# Sheet1.net
KiCad netlist of a schematic drawn in Altium Designer
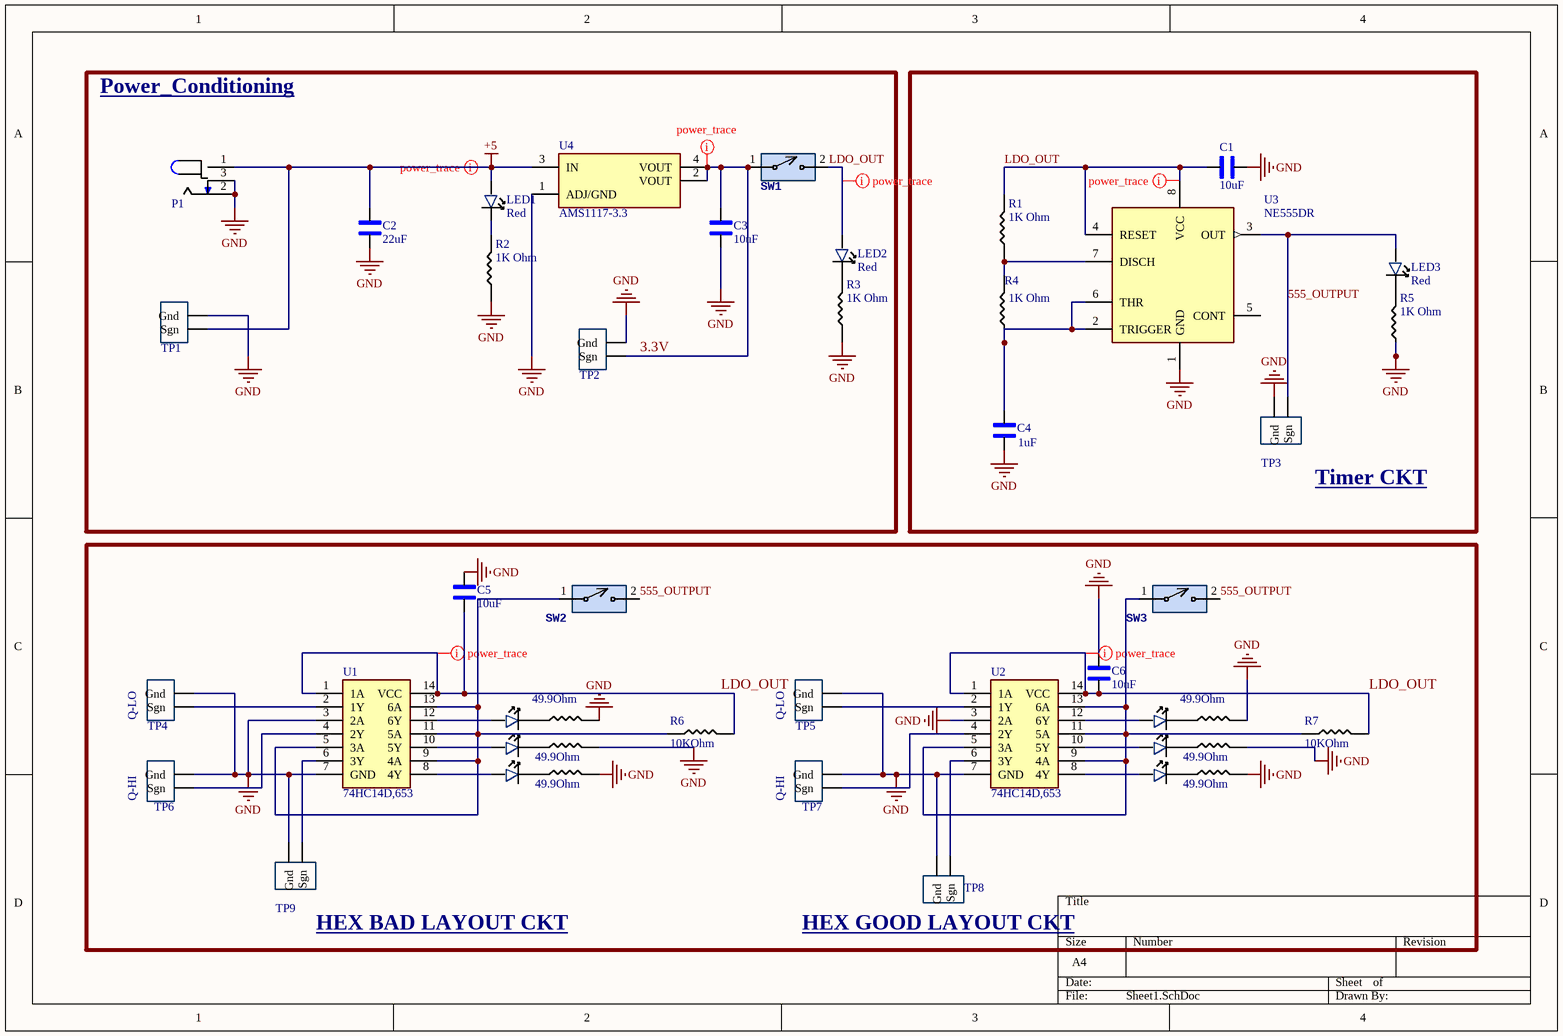
[diagram p0: Sheet1.SchDoc]

(export (version "E")
  (design (tool "Eeschema 10.0.6"))
  (components
    (comp (ref "C1")
      (value "10uF")
      (footprint "0402_Passive_Capacitor")
      (description "10uF ±20% 6.3V X5R 0402 Multilayer Ceramic Capacitors MLCC - SMD/SMT RoHS")
      (fields (field (name "MFR PART #") "CL05A106MQ5NUNC") (field (name "LCSC PART#") "C15525"))
      (libsource (lib "ECEN5730Lib_JLC_2021_07") (part "C_10uF_0402"))
    )
    (comp (ref "C2")
      (value "22uF")
      (footprint "0805_Passive_Capaciitor")
      (description "MULTILAYER CERAMIC CAPACITORS MLCC - SMD/SMT 22UF 25V 0805 ROHS")
      (fields (field (name "MFR PART #") "CL21A226MAQNNNE") (field (name "LCSC PART#") "C45783"))
      (libsource (lib "ECEN5730Lib_JLC_2021_07") (part "C_22uF_0805"))
    )
    (comp (ref "C3")
      (value "10uF")
      (footprint "0402_Passive_Capacitor")
      (description "10uF ±20% 6.3V X5R 0402 Multilayer Ceramic Capacitors MLCC - SMD/SMT RoHS")
      (fields (field (name "MFR PART #") "CL05A106MQ5NUNC") (field (name "LCSC PART#") "C15525"))
      (libsource (lib "ECEN5730Lib_JLC_2021_07") (part "C_10uF_0402"))
    )
    (comp (ref "C4")
      (value "1uF")
      (footprint "1206_Passive_Capacitor")
      (description "MULTILAYER CERAMIC CAPACITORS MLCC - SMD/SMT 1UF 50V 1206 ROHS")
      (fields (field (name "DIGIKEY PART") "399-8150-1-ND") (field (name "MFR PART #") "CL31B105KBHNNNE"))
      (libsource (lib "ECEN5730Lib_JLC_2021_07") (part "C_1uF_1206"))
    )
    (comp (ref "C5")
      (value "10uF")
      (footprint "0402_Passive_Capacitor")
      (description "10uF ±20% 6.3V X5R 0402 Multilayer Ceramic Capacitors MLCC - SMD/SMT RoHS")
      (fields (field (name "MFR PART #") "CL05A106MQ5NUNC") (field (name "LCSC PART#") "C15525"))
      (libsource (lib "ECEN5730Lib_JLC_2021_07") (part "C_10uF_0402"))
    )
    (comp (ref "C6")
      (value "10uF")
      (footprint "0402_Passive_Capacitor")
      (description "10uF ±20% 6.3V X5R 0402 Multilayer Ceramic Capacitors MLCC - SMD/SMT RoHS")
      (fields (field (name "MFR PART #") "CL05A106MQ5NUNC") (field (name "LCSC PART#") "C15525"))
      (libsource (lib "ECEN5730Lib_JLC_2021_07") (part "C_10uF_0402"))
    )
    (comp (ref "LED1")
      (value "Red")
      (footprint "LED_0603")
      (description "LIGHT EMITTING DIODES (LED) RED 520~625NM 90~100MCD@20MA TOP VIEW 0603 ROHS")
      (fields (field (name "MFR PART #") "KT-0603R") (field (name "LCSC PART#") "C2286"))
      (libsource (lib "ECEN5730Lib_JLC_2021_07") (part "LED_RED_0603"))
    )
    (comp (ref "LED2")
      (value "Red")
      (footprint "LED_0603")
      (description "LIGHT EMITTING DIODES (LED) RED 520~625NM 90~100MCD@20MA TOP VIEW 0603 ROHS")
      (fields (field (name "MFR PART #") "KT-0603R") (field (name "LCSC PART#") "C2286"))
      (libsource (lib "ECEN5730Lib_JLC_2021_07") (part "LED_RED_0603"))
    )
    (comp (ref "LED3")
      (value "Red")
      (footprint "LED_0603")
      (description "LIGHT EMITTING DIODES (LED) RED 520~625NM 90~100MCD@20MA TOP VIEW 0603 ROHS")
      (fields (field (name "MFR PART #") "KT-0603R") (field (name "LCSC PART#") "C2286"))
      (libsource (lib "ECEN5730Lib_JLC_2021_07") (part "LED_RED_0603"))
    )
    (comp (ref "LED4")
      (value "KT-0603R")
      (footprint "LED_0603")
      (description "LIGHT EMITTING DIODES (LED) RED 520~625NM 90~100MCD@20MA TOP VIEW 0603 ROHS")
      (fields (field (name "LCSC PART#") "C2286"))
      (libsource (lib "ECEN5730Lib_JLC_2021_07") (part "LED_RED_0603"))
    )
    (comp (ref "LED5")
      (value "KT-0603R")
      (footprint "LED_0603")
      (description "LIGHT EMITTING DIODES (LED) RED 520~625NM 90~100MCD@20MA TOP VIEW 0603 ROHS")
      (fields (field (name "LCSC PART#") "C2286"))
      (libsource (lib "ECEN5730Lib_JLC_2021_07") (part "LED_RED_0603"))
    )
    (comp (ref "LED6")
      (value "KT-0603R")
      (footprint "LED_0603")
      (description "LIGHT EMITTING DIODES (LED) RED 520~625NM 90~100MCD@20MA TOP VIEW 0603 ROHS")
      (fields (field (name "LCSC PART#") "C2286"))
      (libsource (lib "ECEN5730Lib_JLC_2021_07") (part "LED_RED_0603"))
    )
    (comp (ref "LED7")
      (value "KT-0603R")
      (footprint "LED_0603")
      (description "LIGHT EMITTING DIODES (LED) RED 520~625NM 90~100MCD@20MA TOP VIEW 0603 ROHS")
      (fields (field (name "LCSC PART#") "C2286"))
      (libsource (lib "ECEN5730Lib_JLC_2021_07") (part "LED_RED_0603"))
    )
    (comp (ref "LED8")
      (value "KT-0603R")
      (footprint "LED_0603")
      (description "LIGHT EMITTING DIODES (LED) RED 520~625NM 90~100MCD@20MA TOP VIEW 0603 ROHS")
      (fields (field (name "LCSC PART#") "C2286"))
      (libsource (lib "ECEN5730Lib_JLC_2021_07") (part "LED_RED_0603"))
    )
    (comp (ref "LED9")
      (value "KT-0603R")
      (footprint "LED_0603")
      (description "LIGHT EMITTING DIODES (LED) RED 520~625NM 90~100MCD@20MA TOP VIEW 0603 ROHS")
      (fields (field (name "LCSC PART#") "C2286"))
      (libsource (lib "ECEN5730Lib_JLC_2021_07") (part "LED_RED_0603"))
    )
    (comp (ref "P1")
      (value "Power Jack")
      (footprint "Power_Jack")
      (description "Power Barrel Connector Jack 2.10mm ID (0.083\"), 5.50mm OD (0.217\") Through Hole, Right Angle")
      (fields (field (name "DIGIKEY PART") "CP-102A-ND") (field (name "LCSC PART#") "C136744"))
      (libsource (lib "ECEN5730Lib_JLC_2021_07") (part "P_Power Jack"))
    )
    (comp (ref "R1")
      (value "1K Ohm")
      (footprint "1206_Passive_Resitor")
      (description "CHIP RESISTOR - SURFACE MOUNT 1KOHMS ±1% 1/4W 1206 ROHS")
      (fields (field (name "DIGIKEY PART") "RNCP1206FTD1K00CT-ND") (field (name "LCSC PART#") "C4410"))
      (libsource (lib "ECEN5730Lib_JLC_2021_07") (part "R_1K_1206"))
    )
    (comp (ref "R2")
      (value "1K Ohm")
      (footprint "1206_Passive_Resitor")
      (description "CHIP RESISTOR - SURFACE MOUNT 1KOHMS ±1% 1/4W 1206 ROHS")
      (fields (field (name "DIGIKEY PART") "RNCP1206FTD1K00CT-ND") (field (name "LCSC PART#") "C4410"))
      (libsource (lib "ECEN5730Lib_JLC_2021_07") (part "R_1K_1206"))
    )
    (comp (ref "R3")
      (value "1K Ohm")
      (footprint "1206_Passive_Resitor")
      (description "CHIP RESISTOR - SURFACE MOUNT 1KOHMS ±1% 1/4W 1206 ROHS")
      (fields (field (name "DIGIKEY PART") "RNCP1206FTD1K00CT-ND") (field (name "LCSC PART#") "C4410"))
      (libsource (lib "ECEN5730Lib_JLC_2021_07") (part "R_1K_1206"))
    )
    (comp (ref "R4")
      (value "1K Ohm")
      (footprint "1206_Passive_Resitor")
      (description "CHIP RESISTOR - SURFACE MOUNT 1KOHMS ±1% 1/4W 1206 ROHS")
      (fields (field (name "DIGIKEY PART") "RNCP1206FTD1K00CT-ND") (field (name "LCSC PART#") "C4410"))
      (libsource (lib "ECEN5730Lib_JLC_2021_07") (part "R_1K_1206"))
    )
    (comp (ref "R5")
      (value "1K Ohm")
      (footprint "1206_Passive_Resitor")
      (description "CHIP RESISTOR - SURFACE MOUNT 1KOHMS ±1% 1/4W 1206 ROHS")
      (fields (field (name "DIGIKEY PART") "RNCP1206FTD1K00CT-ND") (field (name "LCSC PART#") "C4410"))
      (libsource (lib "ECEN5730Lib_JLC_2021_07") (part "R_1K_1206"))
    )
    (comp (ref "R6")
      (value "10KOhm")
      (footprint "0402_Passive_Resistor")
      (description "CHIP RESISTOR - SURFACE MOUNT 10KOHMS ±1% 1/16W 0402 ROHS")
      (fields (field (name "MFR PART #") "0402WGF1002TCE") (field (name "LCSC PART#") "C25744"))
      (libsource (lib "ECEN5730Lib_JLC_2021_07") (part "R_10KOhm_0402"))
    )
    (comp (ref "R7")
      (value "10KOhm")
      (footprint "0402_Passive_Resistor")
      (description "CHIP RESISTOR - SURFACE MOUNT 10KOHMS ±1% 1/16W 0402 ROHS")
      (fields (field (name "MFR PART #") "0402WGF1002TCE") (field (name "LCSC PART#") "C25744"))
      (libsource (lib "ECEN5730Lib_JLC_2021_07") (part "R_10KOhm_0402"))
    )
    (comp (ref "R8")
      (value "49.9Ohm")
      (footprint "0402_Passive_Resistor")
      (description "CHIP RESISTOR - SURFACE MOUNT 49.9OHMS ±1% 1/16W 0402 ROHS")
      (fields (field (name "MFR PART #") "0402WGF499JTCE") (field (name "LCSC PART#") "C25120"))
      (libsource (lib "ECEN5730Lib_JLC_2021_07") (part "R_50Ohm_0402"))
    )
    (comp (ref "R9")
      (value "49.9Ohm")
      (footprint "0402_Passive_Resistor")
      (description "CHIP RESISTOR - SURFACE MOUNT 49.9OHMS ±1% 1/16W 0402 ROHS")
      (fields (field (name "MFR PART #") "0402WGF499JTCE") (field (name "LCSC PART#") "C25120"))
      (libsource (lib "ECEN5730Lib_JLC_2021_07") (part "R_50Ohm_0402"))
    )
    (comp (ref "R10")
      (value "49.9Ohm")
      (footprint "0402_Passive_Resistor")
      (description "CHIP RESISTOR - SURFACE MOUNT 49.9OHMS ±1% 1/16W 0402 ROHS")
      (fields (field (name "MFR PART #") "0402WGF499JTCE") (field (name "LCSC PART#") "C25120"))
      (libsource (lib "ECEN5730Lib_JLC_2021_07") (part "R_50Ohm_0402"))
    )
    (comp (ref "R11")
      (value "49.9Ohm")
      (footprint "0402_Passive_Resistor")
      (description "CHIP RESISTOR - SURFACE MOUNT 49.9OHMS ±1% 1/16W 0402 ROHS")
      (fields (field (name "MFR PART #") "0402WGF499JTCE") (field (name "LCSC PART#") "C25120"))
      (libsource (lib "ECEN5730Lib_JLC_2021_07") (part "R_50Ohm_0402"))
    )
    (comp (ref "R12")
      (value "49.9Ohm")
      (footprint "0402_Passive_Resistor")
      (description "CHIP RESISTOR - SURFACE MOUNT 49.9OHMS ±1% 1/16W 0402 ROHS")
      (fields (field (name "MFR PART #") "0402WGF499JTCE") (field (name "LCSC PART#") "C25120"))
      (libsource (lib "ECEN5730Lib_JLC_2021_07") (part "R_50Ohm_0402"))
    )
    (comp (ref "R13")
      (value "49.9Ohm")
      (footprint "0402_Passive_Resistor")
      (description "CHIP RESISTOR - SURFACE MOUNT 49.9OHMS ±1% 1/16W 0402 ROHS")
      (fields (field (name "MFR PART #") "0402WGF499JTCE") (field (name "LCSC PART#") "C25120"))
      (libsource (lib "ECEN5730Lib_JLC_2021_07") (part "R_50Ohm_0402"))
    )
    (comp (ref "SW1")
      (value "on_off_switch")
      (footprint "2Pin-Header-Conn")
      (description "2Pin Header")
      (fields (field (name "LCSC PART#") "C124375"))
      (libsource (lib "ECEN5730Lib_JLC_2021_07") (part "SW_2Pin_100mil_Switch"))
    )
    (comp (ref "SW2")
      (value "on_off_switch")
      (footprint "2Pin-Header-Conn")
      (description "2Pin Header")
      (fields (field (name "LCSC PART#") "C124375"))
      (libsource (lib "ECEN5730Lib_JLC_2021_07") (part "SW_2Pin_100mil_Switch"))
    )
    (comp (ref "SW3")
      (value "on_off_switch")
      (footprint "2Pin-Header-Conn")
      (description "2Pin Header")
      (fields (field (name "LCSC PART#") "C124375"))
      (libsource (lib "ECEN5730Lib_JLC_2021_07") (part "SW_2Pin_100mil_Switch"))
    )
    (comp (ref "TP1")
      (value "TP_5V")
      (footprint "TP10x_Probe")
      (description "Test Point 300 mil centers")
      (libsource (lib "ECEN5730Lib_Manual_2021_07") (part "TP_10x_Probe"))
    )
    (comp (ref "TP2")
      (value "TP_5V")
      (footprint "TP10x_Probe")
      (description "Test Point 300 mil centers")
      (libsource (lib "ECEN5730Lib_Manual_2021_07") (part "TP_10x_Probe"))
    )
    (comp (ref "TP3")
      (value "TP_555_OUTPUT")
      (footprint "TP10x_Probe")
      (description "Test Point 300 mil centers")
      (libsource (lib "") (part "TP_10x_Probe_1"))
    )
    (comp (ref "TP4")
      (value "TP_555_OUTPUT")
      (footprint "TP10x_Probe")
      (description "Test Point 300 mil centers")
      (libsource (lib "ECEN5730Lib_Manual_2021_07") (part "TP_10x_Probe"))
    )
    (comp (ref "TP5")
      (value "TP_555_OUTPUT")
      (footprint "TP10x_Probe")
      (description "Test Point 300 mil centers")
      (libsource (lib "ECEN5730Lib_Manual_2021_07") (part "TP_10x_Probe"))
    )
    (comp (ref "TP6")
      (value "TP_555_OUTPUT")
      (footprint "TP10x_Probe")
      (description "Test Point 300 mil centers")
      (libsource (lib "ECEN5730Lib_Manual_2021_07") (part "TP_10x_Probe"))
    )
    (comp (ref "TP7")
      (value "TP_555_OUTPUT")
      (footprint "TP10x_Probe")
      (description "Test Point 300 mil centers")
      (libsource (lib "ECEN5730Lib_Manual_2021_07") (part "TP_10x_Probe"))
    )
    (comp (ref "TP8")
      (value "TP_555_OUTPUT")
      (footprint "TP10x_Probe")
      (description "Test Point 300 mil centers")
      (libsource (lib "") (part "TP_10x_Probe_1"))
    )
    (comp (ref "TP9")
      (value "TP_555_OUTPUT")
      (footprint "TP10x_Probe")
      (description "Test Point 300 mil centers")
      (libsource (lib "") (part "TP_10x_Probe_1"))
    )
    (comp (ref "U1")
      (value "74HC14D,653")
      (footprint "HEX_74AC14")
      (description "Inverter IC 6 Channel Schmitt Trigger 14-SOIC")
      (fields (field (name "LCSC PART#") "C5605"))
      (libsource (lib "ECEN5730Lib_JLC_2021_08") (part "U_7414_HC_Hex"))
    )
    (comp (ref "U2")
      (value "74HC14D,653")
      (footprint "HEX_74AC14")
      (description "Inverter IC 6 Channel Schmitt Trigger 14-SOIC")
      (fields (field (name "LCSC PART#") "C5605"))
      (libsource (lib "ECEN5730Lib_JLC_2021_08") (part "U_7414_HC_Hex"))
    )
    (comp (ref "U3")
      (value "NE555DR")
      (footprint "TS555IDTTR")
      (description "555 Timer SOIC-8_150MIL ROHS 150ns Rise Time")
      (fields (field (name "LCSC PART#") "C7593"))
      (libsource (lib "ECEN5730Lib_JLC_2021_07") (part "U_555_Slow"))
    )
    (comp (ref "U4")
      (value "AMS1117-3.3")
      (footprint "LDO")
      (description "LOW DROPOUT REGULATORS(LDO) POSITIVE FIXED 1.3V @ 800MA 15V 3.3V 1A SOT-223 ROHS")
      (fields (field (name "LCSC PART#") "C6186"))
      (libsource (lib "ECEN5730Lib_JLC_2021_07") (part "PS_AMS_LDO_3v3"))
    )
  )
  (nets
    (net (code "1") (name "+5") (class "Default")
      (node (ref "C2") (pin "2") (pinfunction "2_2") (pintype "passive"))
      (node (ref "LED1") (pin "1") (pinfunction "1_1") (pintype "passive"))
      (node (ref "P1") (pin "1") (pinfunction "1_1") (pintype "power_in"))
      (node (ref "TP1") (pin "1") (pinfunction "Sgn_1") (pintype "passive"))
      (node (ref "U4") (pin "3") (pinfunction "IN_3") (pintype "power_in"))
    )
    (net (code "2") (name "/3.3V") (class "Default")
      (node (ref "C3") (pin "2") (pinfunction "2_2") (pintype "passive"))
      (node (ref "SW1") (pin "1") (pinfunction "1_1") (pintype "passive"))
      (node (ref "TP2") (pin "1") (pinfunction "Sgn_1") (pintype "passive"))
      (node (ref "U4") (pin "2") (pinfunction "VOUT_2") (pintype "power_in"))
      (node (ref "U4") (pin "4") (pinfunction "VOUT_4") (pintype "power_in"))
    )
    (net (code "3") (name "/555_OUTPUT") (class "Default")
      (node (ref "LED3") (pin "1") (pinfunction "1_1") (pintype "passive"))
      (node (ref "SW2") (pin "2") (pinfunction "2_2") (pintype "passive"))
      (node (ref "SW3") (pin "2") (pinfunction "2_2") (pintype "passive"))
      (node (ref "TP3") (pin "1") (pinfunction "Sgn_1") (pintype "passive"))
      (node (ref "U3") (pin "3") (pinfunction "OUT_3") (pintype "output"))
    )
    (net (code "4") (name "/LDO_OUT") (class "Default")
      (node (ref "C1") (pin "2") (pinfunction "2_2") (pintype "passive"))
      (node (ref "C5") (pin "2") (pinfunction "2_2") (pintype "passive"))
      (node (ref "C6") (pin "2") (pinfunction "2_2") (pintype "passive"))
      (node (ref "LED2") (pin "1") (pinfunction "1_1") (pintype "passive"))
      (node (ref "R1") (pin "2") (pinfunction "2_2") (pintype "passive"))
      (node (ref "R6") (pin "2") (pinfunction "2_2") (pintype "passive"))
      (node (ref "R7") (pin "2") (pinfunction "2_2") (pintype "passive"))
      (node (ref "SW1") (pin "2") (pinfunction "2_2") (pintype "passive"))
      (node (ref "U1") (pin "1") (pinfunction "1A_1") (pintype "passive"))
      (node (ref "U1") (pin "14") (pinfunction "VCC_14") (pintype "passive"))
      (node (ref "U2") (pin "1") (pinfunction "1A_1") (pintype "passive"))
      (node (ref "U2") (pin "14") (pinfunction "VCC_14") (pintype "passive"))
      (node (ref "U3") (pin "4") (pinfunction "RESET_4") (pintype "passive"))
      (node (ref "U3") (pin "8") (pinfunction "VCC_8") (pintype "power_in"))
    )
    (net (code "5") (name "GND") (class "Default")
      (node (ref "C1") (pin "1") (pinfunction "1_1") (pintype "passive"))
      (node (ref "C2") (pin "1") (pinfunction "1_1") (pintype "passive"))
      (node (ref "C3") (pin "1") (pinfunction "1_1") (pintype "passive"))
      (node (ref "C4") (pin "1") (pinfunction "1_1") (pintype "passive"))
      (node (ref "C5") (pin "1") (pinfunction "1_1") (pintype "passive"))
      (node (ref "C6") (pin "1") (pinfunction "1_1") (pintype "passive"))
      (node (ref "P1") (pin "2") (pinfunction "2_2") (pintype "power_in"))
      (node (ref "P1") (pin "3") (pinfunction "3_3") (pintype "power_in"))
      (node (ref "R10") (pin "2") (pinfunction "2_2") (pintype "passive"))
      (node (ref "R11") (pin "2") (pinfunction "2_2") (pintype "passive"))
      (node (ref "R12") (pin "2") (pinfunction "2_2") (pintype "passive"))
      (node (ref "R13") (pin "2") (pinfunction "2_2") (pintype "passive"))
      (node (ref "R2") (pin "1") (pinfunction "1_1") (pintype "passive"))
      (node (ref "R3") (pin "1") (pinfunction "1_1") (pintype "passive"))
      (node (ref "R5") (pin "1") (pinfunction "1_1") (pintype "passive"))
      (node (ref "R8") (pin "2") (pinfunction "2_2") (pintype "passive"))
      (node (ref "R9") (pin "2") (pinfunction "2_2") (pintype "passive"))
      (node (ref "TP1") (pin "2") (pinfunction "Gnd_2") (pintype "passive"))
      (node (ref "TP2") (pin "2") (pinfunction "Gnd_2") (pintype "passive"))
      (node (ref "TP3") (pin "2") (pinfunction "Gnd_2") (pintype "passive"))
      (node (ref "TP4") (pin "2") (pinfunction "Gnd_2") (pintype "passive"))
      (node (ref "TP5") (pin "2") (pinfunction "Gnd_2") (pintype "passive"))
      (node (ref "TP6") (pin "2") (pinfunction "Gnd_2") (pintype "passive"))
      (node (ref "TP7") (pin "2") (pinfunction "Gnd_2") (pintype "passive"))
      (node (ref "TP8") (pin "2") (pinfunction "Gnd_2") (pintype "passive"))
      (node (ref "TP9") (pin "2") (pinfunction "Gnd_2") (pintype "passive"))
      (node (ref "U1") (pin "3") (pinfunction "2A_3") (pintype "passive"))
      (node (ref "U1") (pin "7") (pinfunction "GND_7") (pintype "passive"))
      (node (ref "U2") (pin "3") (pinfunction "2A_3") (pintype "passive"))
      (node (ref "U2") (pin "7") (pinfunction "GND_7") (pintype "passive"))
      (node (ref "U3") (pin "1") (pinfunction "GND_1") (pintype "power_in"))
      (node (ref "U4") (pin "1") (pinfunction "ADJ/GND_1") (pintype "passive"))
    )
    (net (code "6") (name "Net-(LED1-Pad2)") (class "Default")
      (node (ref "LED1") (pin "2") (pinfunction "2_2") (pintype "passive"))
      (node (ref "R2") (pin "2") (pinfunction "2_2") (pintype "passive"))
    )
    (net (code "7") (name "Net-(LED2-Pad2)") (class "Default")
      (node (ref "LED2") (pin "2") (pinfunction "2_2") (pintype "passive"))
      (node (ref "R3") (pin "2") (pinfunction "2_2") (pintype "passive"))
    )
    (net (code "8") (name "Net-(LED3-Pad2)") (class "Default")
      (node (ref "LED3") (pin "2") (pinfunction "2_2") (pintype "passive"))
      (node (ref "R5") (pin "2") (pinfunction "2_2") (pintype "passive"))
    )
    (net (code "9") (name "Net-(LED4-Pad2)") (class "Default")
      (node (ref "LED4") (pin "2") (pinfunction "2_2") (pintype "passive"))
      (node (ref "R8") (pin "1") (pinfunction "1_1") (pintype "passive"))
    )
    (net (code "10") (name "Net-(LED5-Pad2)") (class "Default")
      (node (ref "LED5") (pin "2") (pinfunction "2_2") (pintype "passive"))
      (node (ref "R9") (pin "1") (pinfunction "1_1") (pintype "passive"))
    )
    (net (code "11") (name "Net-(LED6-Pad2)") (class "Default")
      (node (ref "LED6") (pin "2") (pinfunction "2_2") (pintype "passive"))
      (node (ref "R12") (pin "1") (pinfunction "1_1") (pintype "passive"))
    )
    (net (code "12") (name "Net-(LED7-Pad2)") (class "Default")
      (node (ref "LED7") (pin "2") (pinfunction "2_2") (pintype "passive"))
      (node (ref "R11") (pin "1") (pinfunction "1_1") (pintype "passive"))
    )
    (net (code "13") (name "Net-(LED8-Pad2)") (class "Default")
      (node (ref "LED8") (pin "2") (pinfunction "2_2") (pintype "passive"))
      (node (ref "R10") (pin "1") (pinfunction "1_1") (pintype "passive"))
    )
    (net (code "14") (name "Net-(LED9-Pad2)") (class "Default")
      (node (ref "LED9") (pin "2") (pinfunction "2_2") (pintype "passive"))
      (node (ref "R13") (pin "1") (pinfunction "1_1") (pintype "passive"))
    )
    (net (code "15") (name "Net-(TP4-Sgn)") (class "Default")
      (node (ref "TP4") (pin "1") (pinfunction "Sgn_1") (pintype "passive"))
      (node (ref "U1") (pin "2") (pinfunction "1Y_2") (pintype "passive"))
    )
    (net (code "16") (name "Net-(TP5-Sgn)") (class "Default")
      (node (ref "TP5") (pin "1") (pinfunction "Sgn_1") (pintype "passive"))
      (node (ref "U2") (pin "2") (pinfunction "1Y_2") (pintype "passive"))
    )
    (net (code "17") (name "Net-(TP6-Sgn)") (class "Default")
      (node (ref "TP6") (pin "1") (pinfunction "Sgn_1") (pintype "passive"))
      (node (ref "U1") (pin "4") (pinfunction "2Y_4") (pintype "passive"))
    )
    (net (code "18") (name "Net-(TP7-Sgn)") (class "Default")
      (node (ref "TP7") (pin "1") (pinfunction "Sgn_1") (pintype "passive"))
      (node (ref "U2") (pin "4") (pinfunction "2Y_4") (pintype "passive"))
    )
    (net (code "19") (name "Net-(TP8-Sgn)") (class "Default")
      (node (ref "TP8") (pin "1") (pinfunction "Sgn_1") (pintype "passive"))
      (node (ref "U2") (pin "6") (pinfunction "3Y_6") (pintype "passive"))
    )
    (net (code "20") (name "Net-(TP9-Sgn)") (class "Default")
      (node (ref "TP9") (pin "1") (pinfunction "Sgn_1") (pintype "passive"))
      (node (ref "U1") (pin "6") (pinfunction "3Y_6") (pintype "passive"))
    )
    (net (code "21") (name "Net-(U1-3A)") (class "Default")
      (node (ref "R6") (pin "1") (pinfunction "1_1") (pintype "passive"))
      (node (ref "SW2") (pin "1") (pinfunction "1_1") (pintype "passive"))
      (node (ref "U1") (pin "11") (pinfunction "5A_11") (pintype "passive"))
      (node (ref "U1") (pin "13") (pinfunction "6A_13") (pintype "passive"))
      (node (ref "U1") (pin "5") (pinfunction "3A_5") (pintype "passive"))
      (node (ref "U1") (pin "9") (pinfunction "4A_9") (pintype "passive"))
    )
    (net (code "22") (name "Net-(U1-4Y)") (class "Default")
      (node (ref "LED8") (pin "1") (pinfunction "1_1") (pintype "passive"))
      (node (ref "U1") (pin "8") (pinfunction "4Y_8") (pintype "passive"))
    )
    (net (code "23") (name "Net-(U1-5Y)") (class "Default")
      (node (ref "LED6") (pin "1") (pinfunction "1_1") (pintype "passive"))
      (node (ref "U1") (pin "10") (pinfunction "5Y_10") (pintype "passive"))
    )
    (net (code "24") (name "Net-(U1-6Y)") (class "Default")
      (node (ref "LED4") (pin "1") (pinfunction "1_1") (pintype "passive"))
      (node (ref "U1") (pin "12") (pinfunction "6Y_12") (pintype "passive"))
    )
    (net (code "25") (name "Net-(U2-3A)") (class "Default")
      (node (ref "R7") (pin "1") (pinfunction "1_1") (pintype "passive"))
      (node (ref "SW3") (pin "1") (pinfunction "1_1") (pintype "passive"))
      (node (ref "U2") (pin "11") (pinfunction "5A_11") (pintype "passive"))
      (node (ref "U2") (pin "13") (pinfunction "6A_13") (pintype "passive"))
      (node (ref "U2") (pin "5") (pinfunction "3A_5") (pintype "passive"))
      (node (ref "U2") (pin "9") (pinfunction "4A_9") (pintype "passive"))
    )
    (net (code "26") (name "Net-(U2-4Y)") (class "Default")
      (node (ref "LED9") (pin "1") (pinfunction "1_1") (pintype "passive"))
      (node (ref "U2") (pin "8") (pinfunction "4Y_8") (pintype "passive"))
    )
    (net (code "27") (name "Net-(U2-5Y)") (class "Default")
      (node (ref "LED7") (pin "1") (pinfunction "1_1") (pintype "passive"))
      (node (ref "U2") (pin "10") (pinfunction "5Y_10") (pintype "passive"))
    )
    (net (code "28") (name "Net-(U2-6Y)") (class "Default")
      (node (ref "LED5") (pin "1") (pinfunction "1_1") (pintype "passive"))
      (node (ref "U2") (pin "12") (pinfunction "6Y_12") (pintype "passive"))
    )
    (net (code "29") (name "Net-(U3-DISCH)") (class "Default")
      (node (ref "R1") (pin "1") (pinfunction "1_1") (pintype "passive"))
      (node (ref "R4") (pin "2") (pinfunction "2_2") (pintype "passive"))
      (node (ref "U3") (pin "7") (pinfunction "DISCH_7") (pintype "passive"))
    )
    (net (code "30") (name "Net-(U3-THR)") (class "Default")
      (node (ref "C4") (pin "2") (pinfunction "2_2") (pintype "passive"))
      (node (ref "R4") (pin "1") (pinfunction "1_1") (pintype "passive"))
      (node (ref "U3") (pin "2") (pinfunction "TRIGGER_2") (pintype "passive"))
      (node (ref "U3") (pin "6") (pinfunction "THR_6") (pintype "passive"))
    )
    (net (code "31") (name "unconnected-(U3-CONT-Pad5)") (class "Default")
      (node (ref "U3") (pin "5") (pinfunction "CONT_5") (pintype "passive"))
    )
  )
)
